# micron_P5.net
KiCad netlist of a schematic drawn in Altium Designer
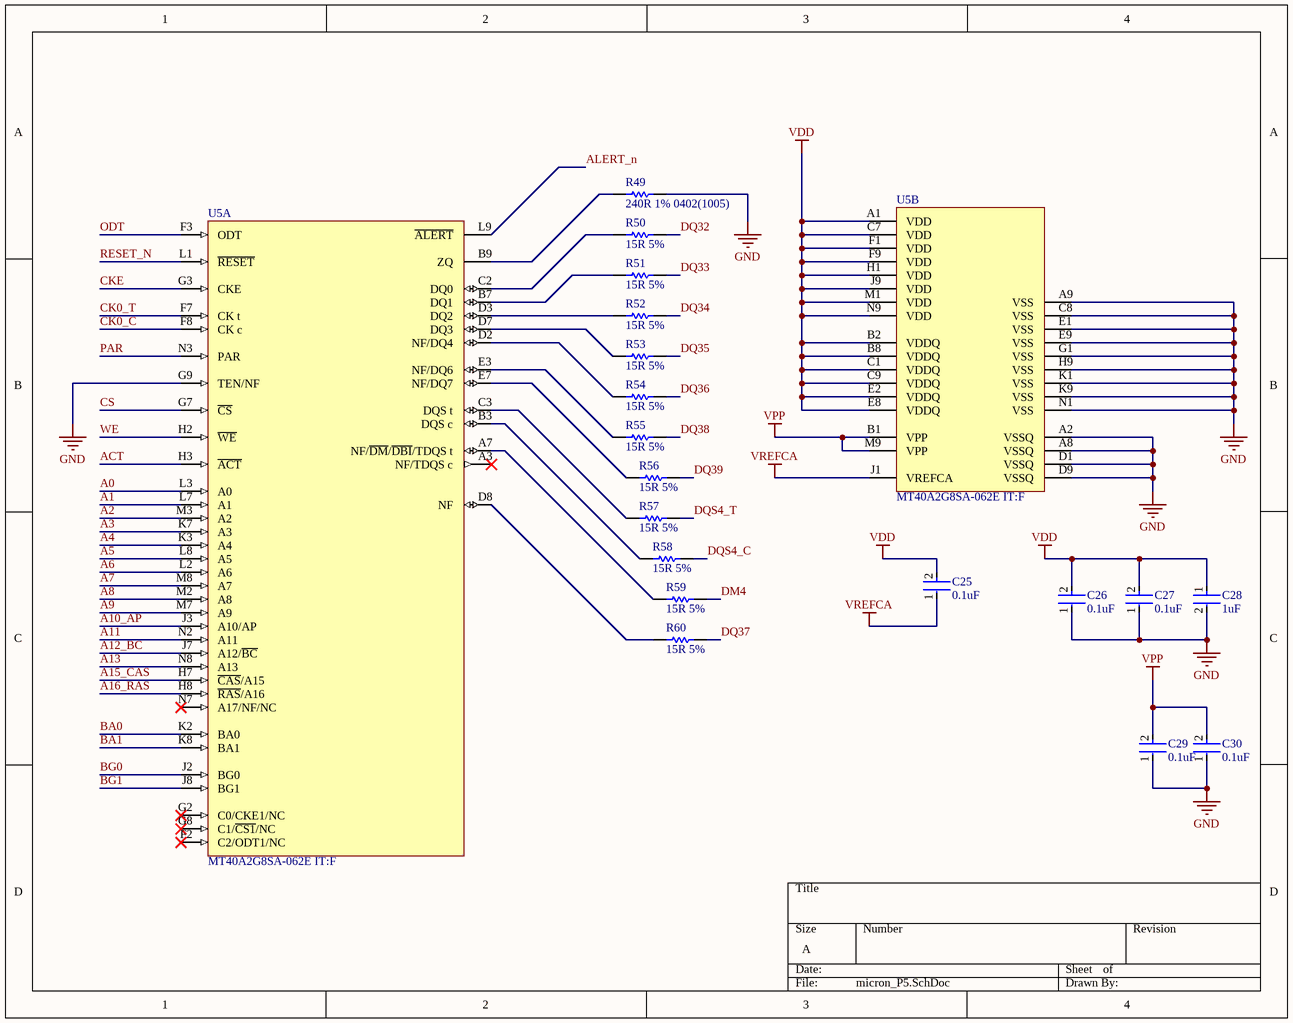
[diagram p0: micron_P5.SchDoc]

(export (version "E")
  (design (tool "Eeschema 10.0.6"))
  (components
    (comp (ref "C25")
      (value "0.1uF")
      (footprint "FP-GRM15-MFG")
      (description "CAP CER 0.1UF 16V X7R 0402")
      (fields (field (name "MANUFACTURER PART NUMBER") "GRM155R71C104KA88D") (field (name "TOLERANCE") "10%"))
      (libsource (lib "Altium Content Vault") (part "236180d848d6139a670b325ea6854c9"))
    )
    (comp (ref "C26")
      (value "0.1uF")
      (footprint "FP-GRM15-MFG")
      (description "CAP CER 0.1UF 16V X7R 0402")
      (fields (field (name "MANUFACTURER PART NUMBER") "GRM155R71C104KA88D") (field (name "TOLERANCE") "10%"))
      (libsource (lib "Altium Content Vault") (part "236180d848d6139a670b325ea6854c9"))
    )
    (comp (ref "C27")
      (value "0.1uF")
      (footprint "FP-GRM15-MFG")
      (description "CAP CER 0.1UF 16V X7R 0402")
      (fields (field (name "MANUFACTURER PART NUMBER") "GRM155R71C104KA88D") (field (name "TOLERANCE") "10%"))
      (libsource (lib "Altium Content Vault") (part "236180d848d6139a670b325ea6854c9"))
    )
    (comp (ref "C28")
      (value "1uF")
      (footprint "FP-CL511-IPC_C")
      (description "Cap Ceramic 1uF 10V X5R ±10% SMD 0402 +85°C Paper T/R")
      (fields (field (name "TOLERANCE") "10%"))
      (libsource (lib "Altium Content Vault") (part "b4654b650e69147ec39a6b967a45e02"))
    )
    (comp (ref "C29")
      (value "0.1uF")
      (footprint "FP-GRM15-MFG")
      (description "CAP CER 0.1UF 16V X7R 0402")
      (fields (field (name "MANUFACTURER PART NUMBER") "GRM155R71C104KA88D") (field (name "TOLERANCE") "10%"))
      (libsource (lib "Altium Content Vault") (part "236180d848d6139a670b325ea6854c9"))
    )
    (comp (ref "C30")
      (value "0.1uF")
      (footprint "FP-GRM15-MFG")
      (description "CAP CER 0.1UF 16V X7R 0402")
      (fields (field (name "MANUFACTURER PART NUMBER") "GRM155R71C104KA88D") (field (name "TOLERANCE") "10%"))
      (libsource (lib "Altium Content Vault") (part "236180d848d6139a670b325ea6854c9"))
    )
    (comp (ref "R49")
      (value "240R 1% 0402(1005)")
      (footprint "RESC0402(1005)_L")
      (description "240R 0.063W 1% 0402 (1005 Metric)  SMD")
      (fields (field (name "POWER") "0.063 W") (field (name "TOLERANCE") "1 %"))
      (libsource (lib "Altium Content Vault") (part "RES"))
    )
    (comp (ref "R50")
      (value "15R 5%")
      (footprint "RESC1005X40X25LL05T10")
      (fields (field (name "MANUFACTURER") "Yageo / Phycomp") (field (name "PART NUMBER") "RC0402FR-0715RL"))
      (libsource (lib "Altium Content Vault") (part "RES"))
    )
    (comp (ref "R51")
      (value "15R 5%")
      (footprint "RESC1005X40X25LL05T10")
      (fields (field (name "MANUFACTURER") "Yageo / Phycomp") (field (name "PART NUMBER") "RC0402FR-0715RL"))
      (libsource (lib "Altium Content Vault") (part "RES"))
    )
    (comp (ref "R52")
      (value "15R 5%")
      (footprint "RESC1005X40X25LL05T10")
      (fields (field (name "MANUFACTURER") "Yageo / Phycomp") (field (name "PART NUMBER") "RC0402FR-0715RL"))
      (libsource (lib "Altium Content Vault") (part "RES"))
    )
    (comp (ref "R53")
      (value "15R 5%")
      (footprint "RESC1005X40X25LL05T10")
      (fields (field (name "MANUFACTURER") "Yageo / Phycomp") (field (name "PART NUMBER") "RC0402FR-0715RL"))
      (libsource (lib "Altium Content Vault") (part "RES"))
    )
    (comp (ref "R54")
      (value "15R 5%")
      (footprint "RESC1005X40X25LL05T10")
      (fields (field (name "MANUFACTURER") "Yageo / Phycomp") (field (name "PART NUMBER") "RC0402FR-0715RL"))
      (libsource (lib "Altium Content Vault") (part "RES"))
    )
    (comp (ref "R55")
      (value "15R 5%")
      (footprint "RESC1005X40X25LL05T10")
      (fields (field (name "MANUFACTURER") "Yageo / Phycomp") (field (name "PART NUMBER") "RC0402FR-0715RL"))
      (libsource (lib "Altium Content Vault") (part "RES"))
    )
    (comp (ref "R56")
      (value "15R 5%")
      (footprint "RESC1005X40X25LL05T10")
      (fields (field (name "MANUFACTURER") "Yageo / Phycomp") (field (name "PART NUMBER") "RC0402FR-0715RL"))
      (libsource (lib "Altium Content Vault") (part "RES"))
    )
    (comp (ref "R57")
      (value "15R 5%")
      (footprint "RESC1005X40X25LL05T10")
      (fields (field (name "MANUFACTURER") "Yageo / Phycomp") (field (name "PART NUMBER") "RC0402FR-0715RL"))
      (libsource (lib "Altium Content Vault") (part "RES"))
    )
    (comp (ref "R58")
      (value "15R 5%")
      (footprint "RESC1005X40X25LL05T10")
      (fields (field (name "MANUFACTURER") "Yageo / Phycomp") (field (name "PART NUMBER") "RC0402FR-0715RL"))
      (libsource (lib "Altium Content Vault") (part "RES"))
    )
    (comp (ref "R59")
      (value "15R 5%")
      (footprint "RESC1005X40X25LL05T10")
      (fields (field (name "MANUFACTURER") "Yageo / Phycomp") (field (name "PART NUMBER") "RC0402FR-0715RL"))
      (libsource (lib "Altium Content Vault") (part "RES"))
    )
    (comp (ref "R60")
      (value "15R 5%")
      (footprint "RESC1005X40X25LL05T10")
      (fields (field (name "MANUFACTURER") "Yageo / Phycomp") (field (name "PART NUMBER") "RC0402FR-0715RL"))
      (libsource (lib "Altium Content Vault") (part "RES"))
    )
    (comp (ref "U5")
      (value "MT40A2G8SA-062E IT:F")
      (footprint "SA_MFG")
      (description "DRAMChip DDR4 SDRAM 16Gbit 2Gx8 1.2V 78-Pin FBGA Tray")
      (libsource (lib "Altium Content Vault") (part "d28cb998757b614ee3280f10a38a3b1"))
    )
  )
  (nets
    (net (code "1") (name "/A0") (class "Default")
      (node (ref "U5") (pin "L3") (pinfunction "A0_L3") (pintype "input"))
    )
    (net (code "2") (name "/A1") (class "Default")
      (node (ref "U5") (pin "L7") (pinfunction "A1_L7") (pintype "input"))
    )
    (net (code "3") (name "/A2") (class "Default")
      (node (ref "U5") (pin "M3") (pinfunction "A2_M3") (pintype "input"))
    )
    (net (code "4") (name "/A3") (class "Default")
      (node (ref "U5") (pin "K7") (pinfunction "A3_K7") (pintype "input"))
    )
    (net (code "5") (name "/A4") (class "Default")
      (node (ref "U5") (pin "K3") (pinfunction "A4_K3") (pintype "input"))
    )
    (net (code "6") (name "/A5") (class "Default")
      (node (ref "U5") (pin "L8") (pinfunction "A5_L8") (pintype "input"))
    )
    (net (code "7") (name "/A6") (class "Default")
      (node (ref "U5") (pin "L2") (pinfunction "A6_L2") (pintype "input"))
    )
    (net (code "8") (name "/A7") (class "Default")
      (node (ref "U5") (pin "M8") (pinfunction "A7_M8") (pintype "input"))
    )
    (net (code "9") (name "/A8") (class "Default")
      (node (ref "U5") (pin "M2") (pinfunction "A8_M2") (pintype "input"))
    )
    (net (code "10") (name "/A9") (class "Default")
      (node (ref "U5") (pin "M7") (pinfunction "A9_M7") (pintype "input"))
    )
    (net (code "11") (name "/A10_AP") (class "Default")
      (node (ref "U5") (pin "J3") (pinfunction "A10/AP_J3") (pintype "input"))
    )
    (net (code "12") (name "/A11") (class "Default")
      (node (ref "U5") (pin "N2") (pinfunction "A11_N2") (pintype "input"))
    )
    (net (code "13") (name "/A12_BC") (class "Default")
      (node (ref "U5") (pin "J7") (pinfunction "A12/~{BC}_J7") (pintype "input"))
    )
    (net (code "14") (name "/A13") (class "Default")
      (node (ref "U5") (pin "N8") (pinfunction "A13_N8") (pintype "input"))
    )
    (net (code "15") (name "/A15_CAS") (class "Default")
      (node (ref "U5") (pin "H7") (pinfunction "~{CAS}/A15_H7") (pintype "input"))
    )
    (net (code "16") (name "/A16_RAS") (class "Default")
      (node (ref "U5") (pin "H8") (pinfunction "~{RAS}/A16_H8") (pintype "input"))
    )
    (net (code "17") (name "/ACT") (class "Default")
      (node (ref "U5") (pin "H3") (pinfunction "~{ACT}_H3") (pintype "input"))
    )
    (net (code "18") (name "/ALERT_n") (class "Default")
      (node (ref "U5") (pin "L9") (pinfunction "~{ALERT}_L9") (pintype "open_collector"))
    )
    (net (code "19") (name "/BA0") (class "Default")
      (node (ref "U5") (pin "K2") (pinfunction "BA0_K2") (pintype "input"))
    )
    (net (code "20") (name "/BA1") (class "Default")
      (node (ref "U5") (pin "K8") (pinfunction "BA1_K8") (pintype "input"))
    )
    (net (code "21") (name "/BG0") (class "Default")
      (node (ref "U5") (pin "J2") (pinfunction "BG0_J2") (pintype "input"))
    )
    (net (code "22") (name "/BG1") (class "Default")
      (node (ref "U5") (pin "J8") (pinfunction "BG1_J8") (pintype "input"))
    )
    (net (code "23") (name "/CK0_C") (class "Default")
      (node (ref "U5") (pin "F8") (pinfunction "CK_c_F8") (pintype "input"))
    )
    (net (code "24") (name "/CK0_T") (class "Default")
      (node (ref "U5") (pin "F7") (pinfunction "CK_t_F7") (pintype "input"))
    )
    (net (code "25") (name "/CKE") (class "Default")
      (node (ref "U5") (pin "G3") (pinfunction "CKE_G3") (pintype "input"))
    )
    (net (code "26") (name "/CS") (class "Default")
      (node (ref "U5") (pin "G7") (pinfunction "~{CS}_G7") (pintype "input"))
    )
    (net (code "27") (name "/DM4") (class "Default")
      (node (ref "R59") (pin "2") (pinfunction "2_2") (pintype "passive"))
    )
    (net (code "28") (name "/DQ32") (class "Default")
      (node (ref "R50") (pin "2") (pinfunction "2_2") (pintype "passive"))
    )
    (net (code "29") (name "/DQ33") (class "Default")
      (node (ref "R51") (pin "2") (pinfunction "2_2") (pintype "passive"))
    )
    (net (code "30") (name "/DQ34") (class "Default")
      (node (ref "R52") (pin "2") (pinfunction "2_2") (pintype "passive"))
    )
    (net (code "31") (name "/DQ35") (class "Default")
      (node (ref "R53") (pin "2") (pinfunction "2_2") (pintype "passive"))
    )
    (net (code "32") (name "/DQ36") (class "Default")
      (node (ref "R54") (pin "2") (pinfunction "2_2") (pintype "passive"))
    )
    (net (code "33") (name "/DQ37") (class "Default")
      (node (ref "R60") (pin "2") (pinfunction "2_2") (pintype "passive"))
    )
    (net (code "34") (name "/DQ38") (class "Default")
      (node (ref "R55") (pin "2") (pinfunction "2_2") (pintype "passive"))
    )
    (net (code "35") (name "/DQ39") (class "Default")
      (node (ref "R56") (pin "2") (pinfunction "2_2") (pintype "passive"))
    )
    (net (code "36") (name "/DQS4_C") (class "Default")
      (node (ref "R58") (pin "2") (pinfunction "2_2") (pintype "passive"))
    )
    (net (code "37") (name "/DQS4_T") (class "Default")
      (node (ref "R57") (pin "2") (pinfunction "2_2") (pintype "passive"))
    )
    (net (code "38") (name "/ODT") (class "Default")
      (node (ref "U5") (pin "F3") (pinfunction "ODT_F3") (pintype "input"))
    )
    (net (code "39") (name "/PAR") (class "Default")
      (node (ref "U5") (pin "N3") (pinfunction "PAR_N3") (pintype "input"))
    )
    (net (code "40") (name "/RESET_N") (class "Default")
      (node (ref "U5") (pin "L1") (pinfunction "~{RESET}_L1") (pintype "input"))
    )
    (net (code "41") (name "/WE") (class "Default")
      (node (ref "U5") (pin "H2") (pinfunction "~{WE}_H2") (pintype "input"))
    )
    (net (code "42") (name "GND") (class "Default")
      (node (ref "C26") (pin "1") (pinfunction "1_1") (pintype "passive"))
      (node (ref "C27") (pin "1") (pinfunction "1_1") (pintype "passive"))
      (node (ref "C28") (pin "2") (pinfunction "2_2") (pintype "passive"))
      (node (ref "C29") (pin "1") (pinfunction "1_1") (pintype "passive"))
      (node (ref "C30") (pin "1") (pinfunction "1_1") (pintype "passive"))
      (node (ref "R49") (pin "2") (pinfunction "2_2") (pintype "passive"))
      (node (ref "U5") (pin "A2") (pinfunction "VSSQ_A2") (pintype "power_in"))
      (node (ref "U5") (pin "A8") (pinfunction "VSSQ_A8") (pintype "power_in"))
      (node (ref "U5") (pin "A9") (pinfunction "VSS_A9") (pintype "power_in"))
      (node (ref "U5") (pin "C8") (pinfunction "VSS_C8") (pintype "power_in"))
      (node (ref "U5") (pin "D1") (pinfunction "VSSQ_D1") (pintype "power_in"))
      (node (ref "U5") (pin "D9") (pinfunction "VSSQ_D9") (pintype "power_in"))
      (node (ref "U5") (pin "E1") (pinfunction "VSS_E1") (pintype "power_in"))
      (node (ref "U5") (pin "E9") (pinfunction "VSS_E9") (pintype "power_in"))
      (node (ref "U5") (pin "G1") (pinfunction "VSS_G1") (pintype "power_in"))
      (node (ref "U5") (pin "G9") (pinfunction "TEN/NF_G9") (pintype "input"))
      (node (ref "U5") (pin "H9") (pinfunction "VSS_H9") (pintype "power_in"))
      (node (ref "U5") (pin "K1") (pinfunction "VSS_K1") (pintype "power_in"))
      (node (ref "U5") (pin "K9") (pinfunction "VSS_K9") (pintype "power_in"))
      (node (ref "U5") (pin "N1") (pinfunction "VSS_N1") (pintype "power_in"))
    )
    (net (code "43") (name "Net-(U5A-DQ0)") (class "Default")
      (node (ref "R50") (pin "1") (pinfunction "1_1") (pintype "passive"))
      (node (ref "U5") (pin "C2") (pinfunction "DQ0_C2") (pintype "bidirectional"))
    )
    (net (code "44") (name "Net-(U5A-DQ1)") (class "Default")
      (node (ref "R51") (pin "1") (pinfunction "1_1") (pintype "passive"))
      (node (ref "U5") (pin "B7") (pinfunction "DQ1_B7") (pintype "bidirectional"))
    )
    (net (code "45") (name "Net-(U5A-DQ2)") (class "Default")
      (node (ref "R52") (pin "1") (pinfunction "1_1") (pintype "passive"))
      (node (ref "U5") (pin "D3") (pinfunction "DQ2_D3") (pintype "bidirectional"))
    )
    (net (code "46") (name "Net-(U5A-DQ3)") (class "Default")
      (node (ref "R53") (pin "1") (pinfunction "1_1") (pintype "passive"))
      (node (ref "U5") (pin "D7") (pinfunction "DQ3_D7") (pintype "bidirectional"))
    )
    (net (code "47") (name "Net-(U5A-DQS_c)") (class "Default")
      (node (ref "R58") (pin "1") (pinfunction "1_1") (pintype "passive"))
      (node (ref "U5") (pin "B3") (pinfunction "DQS_c_B3") (pintype "bidirectional"))
    )
    (net (code "48") (name "Net-(U5A-DQS_t)") (class "Default")
      (node (ref "R57") (pin "1") (pinfunction "1_1") (pintype "passive"))
      (node (ref "U5") (pin "C3") (pinfunction "DQS_t_C3") (pintype "bidirectional"))
    )
    (net (code "49") (name "Net-(U5A-NF)") (class "Default")
      (node (ref "R60") (pin "1") (pinfunction "1_1") (pintype "passive"))
      (node (ref "U5") (pin "D8") (pinfunction "NF_D8") (pintype "bidirectional"))
    )
    (net (code "50") (name "Net-(U5A-NF{slash}DQ4)") (class "Default")
      (node (ref "R54") (pin "1") (pinfunction "1_1") (pintype "passive"))
      (node (ref "U5") (pin "D2") (pinfunction "NF/DQ4_D2") (pintype "bidirectional"))
    )
    (net (code "51") (name "Net-(U5A-NF{slash}DQ6)") (class "Default")
      (node (ref "R55") (pin "1") (pinfunction "1_1") (pintype "passive"))
      (node (ref "U5") (pin "E3") (pinfunction "NF/DQ6_E3") (pintype "bidirectional"))
    )
    (net (code "52") (name "Net-(U5A-NF{slash}DQ7)") (class "Default")
      (node (ref "R56") (pin "1") (pinfunction "1_1") (pintype "passive"))
      (node (ref "U5") (pin "E7") (pinfunction "NF/DQ7_E7") (pintype "bidirectional"))
    )
    (net (code "53") (name "Net-(U5A-NF{slash}~{DM}{slash}~{DBI}{slash}TDQS_t)") (class "Default")
      (node (ref "R59") (pin "1") (pinfunction "1_1") (pintype "passive"))
      (node (ref "U5") (pin "A7") (pinfunction "NF/~{DM}/~{DBI}/TDQS_t_A7") (pintype "bidirectional"))
    )
    (net (code "54") (name "Net-(U5A-ZQ)") (class "Default")
      (node (ref "R49") (pin "1") (pinfunction "1_1") (pintype "passive"))
      (node (ref "U5") (pin "B9") (pinfunction "ZQ_B9") (pintype "passive"))
    )
    (net (code "55") (name "VDD") (class "Default")
      (node (ref "C25") (pin "2") (pinfunction "2_2") (pintype "passive"))
      (node (ref "C26") (pin "2") (pinfunction "2_2") (pintype "passive"))
      (node (ref "C27") (pin "2") (pinfunction "2_2") (pintype "passive"))
      (node (ref "C28") (pin "1") (pinfunction "1_1") (pintype "passive"))
      (node (ref "U5") (pin "A1") (pinfunction "VDD_A1") (pintype "power_in"))
      (node (ref "U5") (pin "B2") (pinfunction "VDDQ_B2") (pintype "power_in"))
      (node (ref "U5") (pin "B8") (pinfunction "VDDQ_B8") (pintype "power_in"))
      (node (ref "U5") (pin "C1") (pinfunction "VDDQ_C1") (pintype "power_in"))
      (node (ref "U5") (pin "C7") (pinfunction "VDD_C7") (pintype "power_in"))
      (node (ref "U5") (pin "C9") (pinfunction "VDDQ_C9") (pintype "power_in"))
      (node (ref "U5") (pin "E2") (pinfunction "VDDQ_E2") (pintype "power_in"))
      (node (ref "U5") (pin "E8") (pinfunction "VDDQ_E8") (pintype "power_in"))
      (node (ref "U5") (pin "F1") (pinfunction "VDD_F1") (pintype "power_in"))
      (node (ref "U5") (pin "F9") (pinfunction "VDD_F9") (pintype "power_in"))
      (node (ref "U5") (pin "H1") (pinfunction "VDD_H1") (pintype "power_in"))
      (node (ref "U5") (pin "J9") (pinfunction "VDD_J9") (pintype "power_in"))
      (node (ref "U5") (pin "M1") (pinfunction "VDD_M1") (pintype "power_in"))
      (node (ref "U5") (pin "N9") (pinfunction "VDD_N9") (pintype "power_in"))
    )
    (net (code "56") (name "VPP") (class "Default")
      (node (ref "C29") (pin "2") (pinfunction "2_2") (pintype "passive"))
      (node (ref "C30") (pin "2") (pinfunction "2_2") (pintype "passive"))
      (node (ref "U5") (pin "B1") (pinfunction "VPP_B1") (pintype "power_in"))
      (node (ref "U5") (pin "M9") (pinfunction "VPP_M9") (pintype "power_in"))
    )
    (net (code "57") (name "VREFCA") (class "Default")
      (node (ref "C25") (pin "1") (pinfunction "1_1") (pintype "passive"))
      (node (ref "U5") (pin "J1") (pinfunction "VREFCA_J1") (pintype "power_in"))
    )
    (net (code "58") (name "unconnected-(U5A-A17{slash}NF{slash}NC-PadN7)") (class "Default")
      (node (ref "U5") (pin "N7") (pinfunction "A17/NF/NC_N7") (pintype "input+no_connect"))
    )
    (net (code "59") (name "unconnected-(U5A-C0{slash}CKE1{slash}NC-PadG2)") (class "Default")
      (node (ref "U5") (pin "G2") (pinfunction "C0/CKE1/NC_G2") (pintype "input+no_connect"))
    )
    (net (code "60") (name "unconnected-(U5A-C1{slash}~{CS1}{slash}NC-PadG8)") (class "Default")
      (node (ref "U5") (pin "G8") (pinfunction "C1/~{CS1}/NC_G8") (pintype "input+no_connect"))
    )
    (net (code "61") (name "unconnected-(U5A-C2{slash}ODT1{slash}NC-PadF2)") (class "Default")
      (node (ref "U5") (pin "F2") (pinfunction "C2/ODT1/NC_F2") (pintype "input+no_connect"))
    )
    (net (code "62") (name "unconnected-(U5A-NF{slash}TDQS_c-PadA3)") (class "Default")
      (node (ref "U5") (pin "A3") (pinfunction "NF/TDQS_c_A3") (pintype "output+no_connect"))
    )
  )
)
